# ZeroCrossDetector.net
KiCad netlist of a schematic drawn in Altium Designer
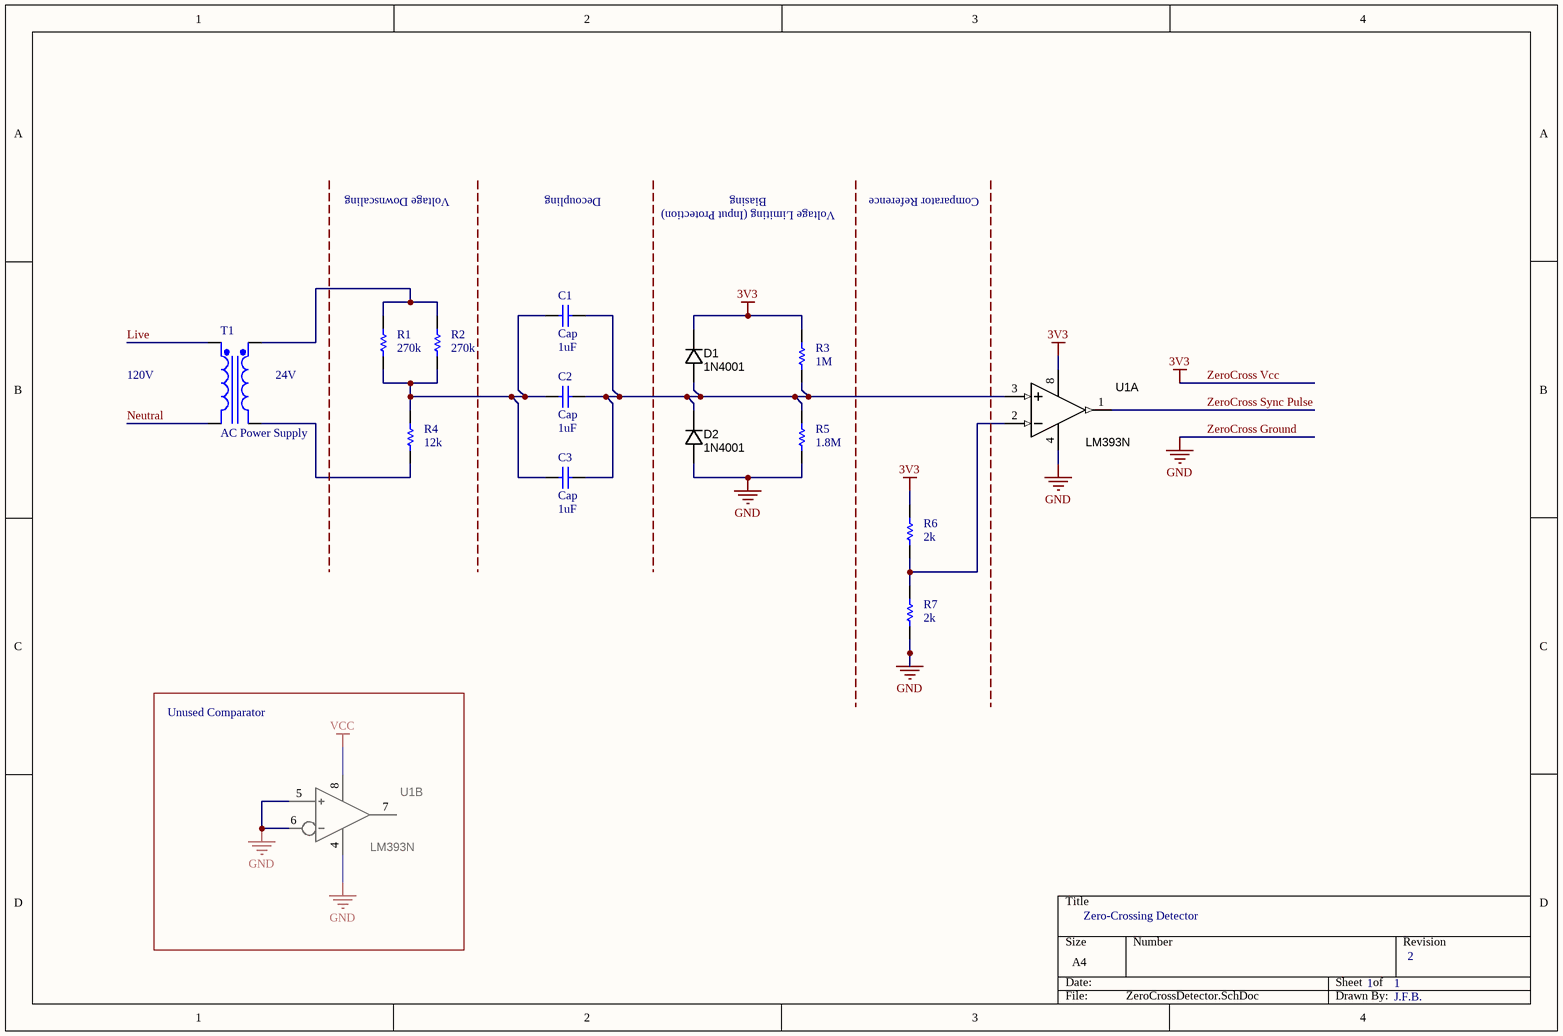
[diagram p0: ZeroCrossDetector.SchDoc]

(export (version "E")
  (design (tool "Eeschema 10.0.6"))
  (components
    (comp (ref "C1")
      (value "Cap")
      (footprint "RAD-0.3")
      (description "Capacitor")
      (fields (field (name "ALTIUM_VALUE") "1uF") (field (name "PUBLISHER") "Altium Limited"))
      (libsource (lib "Miscellaneous Devices") (part "Cap"))
    )
    (comp (ref "C2")
      (value "Cap")
      (footprint "RAD-0.3")
      (description "Capacitor")
      (fields (field (name "ALTIUM_VALUE") "1uF") (field (name "PUBLISHER") "Altium Limited"))
      (libsource (lib "Miscellaneous Devices") (part "Cap"))
    )
    (comp (ref "C3")
      (value "Cap")
      (footprint "RAD-0.3")
      (description "Capacitor")
      (fields (field (name "ALTIUM_VALUE") "1uF") (field (name "PUBLISHER") "Altium Limited"))
      (libsource (lib "Miscellaneous Devices") (part "Cap"))
    )
    (comp (ref "D1")
      (value "1N4001")
      (footprint "DO-41")
      (description "Diode 1N4007 1A 1000V THD")
      (libsource (lib "PBL - Diodes") (part "DIODE_1N4007_1000V_1.0A_DO-41"))
    )
    (comp (ref "D2")
      (value "1N4001")
      (footprint "DO-41")
      (description "Diode 1N4007 1A 1000V THD")
      (libsource (lib "PBL - Diodes") (part "DIODE_1N4007_1000V_1.0A_DO-41"))
    )
    (comp (ref "R1")
      (value "270k")
      (footprint "AXIAL-0.3")
      (description "Resistor")
      (fields (field (name "PUBLISHER") "Altium Limited"))
      (libsource (lib "Miscellaneous Devices") (part "Res1"))
    )
    (comp (ref "R2")
      (value "270k")
      (footprint "AXIAL-0.3")
      (description "Resistor")
      (fields (field (name "PUBLISHER") "Altium Limited"))
      (libsource (lib "Miscellaneous Devices") (part "Res1"))
    )
    (comp (ref "R3")
      (value "1M")
      (footprint "AXIAL-0.3")
      (description "Resistor")
      (fields (field (name "PUBLISHER") "Altium Limited"))
      (libsource (lib "Miscellaneous Devices") (part "Res1"))
    )
    (comp (ref "R4")
      (value "12k")
      (footprint "AXIAL-0.3")
      (description "Resistor")
      (fields (field (name "PUBLISHER") "Altium Limited"))
      (libsource (lib "Miscellaneous Devices") (part "Res1"))
    )
    (comp (ref "R5")
      (value "1.8M")
      (footprint "AXIAL-0.3")
      (description "Resistor")
      (fields (field (name "PUBLISHER") "Altium Limited"))
      (libsource (lib "Miscellaneous Devices") (part "Res1"))
    )
    (comp (ref "R6")
      (value "2k")
      (footprint "AXIAL-0.3")
      (description "Resistor")
      (fields (field (name "PUBLISHER") "Altium Limited"))
      (libsource (lib "Miscellaneous Devices") (part "Res1"))
    )
    (comp (ref "R7")
      (value "2k")
      (footprint "AXIAL-0.3")
      (description "Resistor")
      (fields (field (name "PUBLISHER") "Altium Limited"))
      (libsource (lib "Miscellaneous Devices") (part "Res1"))
    )
    (comp (ref "T1")
      (value "AC Power Supply")
      (footprint "TRF_4")
      (description "Transformer (Ideal)")
      (fields (field (name "PUBLISHER") "Altium Limited"))
      (libsource (lib "Miscellaneous Devices") (part "Trans Ideal"))
    )
    (comp (ref "U1")
      (value "LM393N")
      (description "Fairchild LM393N Comparator")
      (libsource (lib "PBL - Integrated Circuits") (part "IC_AMP+COMPAR_TLV2702"))
    )
  )
  (nets
    (net (code "1") (name "/Live") (class "Default")
      (node (ref "T1") (pin "1") (pinfunction "Pri+_1") (pintype "passive"))
    )
    (net (code "2") (name "/Neutral") (class "Default")
      (node (ref "T1") (pin "2") (pinfunction "Pri-_2") (pintype "passive"))
    )
    (net (code "3") (name "/ZeroCross Sync Pulse") (class "Default")
      (node (ref "U1") (pin "1") (pinfunction "Aout_1") (pintype "output"))
    )
    (net (code "4") (name "3V3") (class "Default")
      (node (ref "D1") (pin "K") (pinfunction "K_K") (pintype "passive"))
      (node (ref "R3") (pin "2") (pinfunction "2_2") (pintype "passive"))
      (node (ref "R6") (pin "2") (pinfunction "2_2") (pintype "passive"))
      (node (ref "U1") (pin "8") (pinfunction "+Vs_8") (pintype "power_in"))
    )
    (net (code "5") (name "GND") (class "Default")
      (node (ref "D2") (pin "A") (pinfunction "A_A") (pintype "passive"))
      (node (ref "R5") (pin "1") (pinfunction "1_1") (pintype "passive"))
      (node (ref "R7") (pin "1") (pinfunction "1_1") (pintype "passive"))
      (node (ref "U1") (pin "4") (pinfunction "-Vs_4") (pintype "power_in"))
      (node (ref "U1") (pin "5") (pinfunction "CIN_+_5") (pintype "passive"))
      (node (ref "U1") (pin "6") (pinfunction "_CIN-_6") (pintype "passive"))
    )
    (net (code "6") (name "Net-(C1-Pad1)") (class "Default")
      (node (ref "C1") (pin "1") (pinfunction "1_1") (pintype "passive"))
      (node (ref "C2") (pin "1") (pinfunction "1_1") (pintype "passive"))
      (node (ref "C3") (pin "1") (pinfunction "1_1") (pintype "passive"))
      (node (ref "R1") (pin "1") (pinfunction "1_1") (pintype "passive"))
      (node (ref "R2") (pin "1") (pinfunction "1_1") (pintype "passive"))
      (node (ref "R4") (pin "2") (pinfunction "2_2") (pintype "passive"))
    )
    (net (code "7") (name "Net-(T1-Sec+)") (class "Default")
      (node (ref "R1") (pin "2") (pinfunction "2_2") (pintype "passive"))
      (node (ref "R2") (pin "2") (pinfunction "2_2") (pintype "passive"))
      (node (ref "T1") (pin "3") (pinfunction "Sec+_3") (pintype "passive"))
    )
    (net (code "8") (name "Net-(T1-Sec-)") (class "Default")
      (node (ref "R4") (pin "1") (pinfunction "1_1") (pintype "passive"))
      (node (ref "T1") (pin "4") (pinfunction "Sec-_4") (pintype "passive"))
    )
    (net (code "9") (name "Net-(U1A-AIN_+)") (class "Default")
      (node (ref "C1") (pin "2") (pinfunction "2_2") (pintype "passive"))
      (node (ref "C2") (pin "2") (pinfunction "2_2") (pintype "passive"))
      (node (ref "C3") (pin "2") (pinfunction "2_2") (pintype "passive"))
      (node (ref "D1") (pin "A") (pinfunction "A_A") (pintype "passive"))
      (node (ref "D2") (pin "K") (pinfunction "K_K") (pintype "passive"))
      (node (ref "R3") (pin "1") (pinfunction "1_1") (pintype "passive"))
      (node (ref "R5") (pin "2") (pinfunction "2_2") (pintype "passive"))
      (node (ref "U1") (pin "3") (pinfunction "AIN_+_3") (pintype "input"))
    )
    (net (code "10") (name "Net-(U1A-AIN_-)") (class "Default")
      (node (ref "R6") (pin "1") (pinfunction "1_1") (pintype "passive"))
      (node (ref "R7") (pin "2") (pinfunction "2_2") (pintype "passive"))
      (node (ref "U1") (pin "2") (pinfunction "AIN_-_2") (pintype "input"))
    )
    (net (code "11") (name "VCC") (class "Default")
      (node (ref "U1") (pin "8") (pinfunction "+Vs_8") (pintype "power_in"))
    )
    (net (code "12") (name "unconnected-(U1B-Cout-Pad7)") (class "Default")
      (node (ref "U1") (pin "7") (pinfunction "Cout_7") (pintype "passive"))
    )
  )
)
